# diceee123_2021-04-25_1.net
KiCad netlist of a schematic drawn in EasyEDA
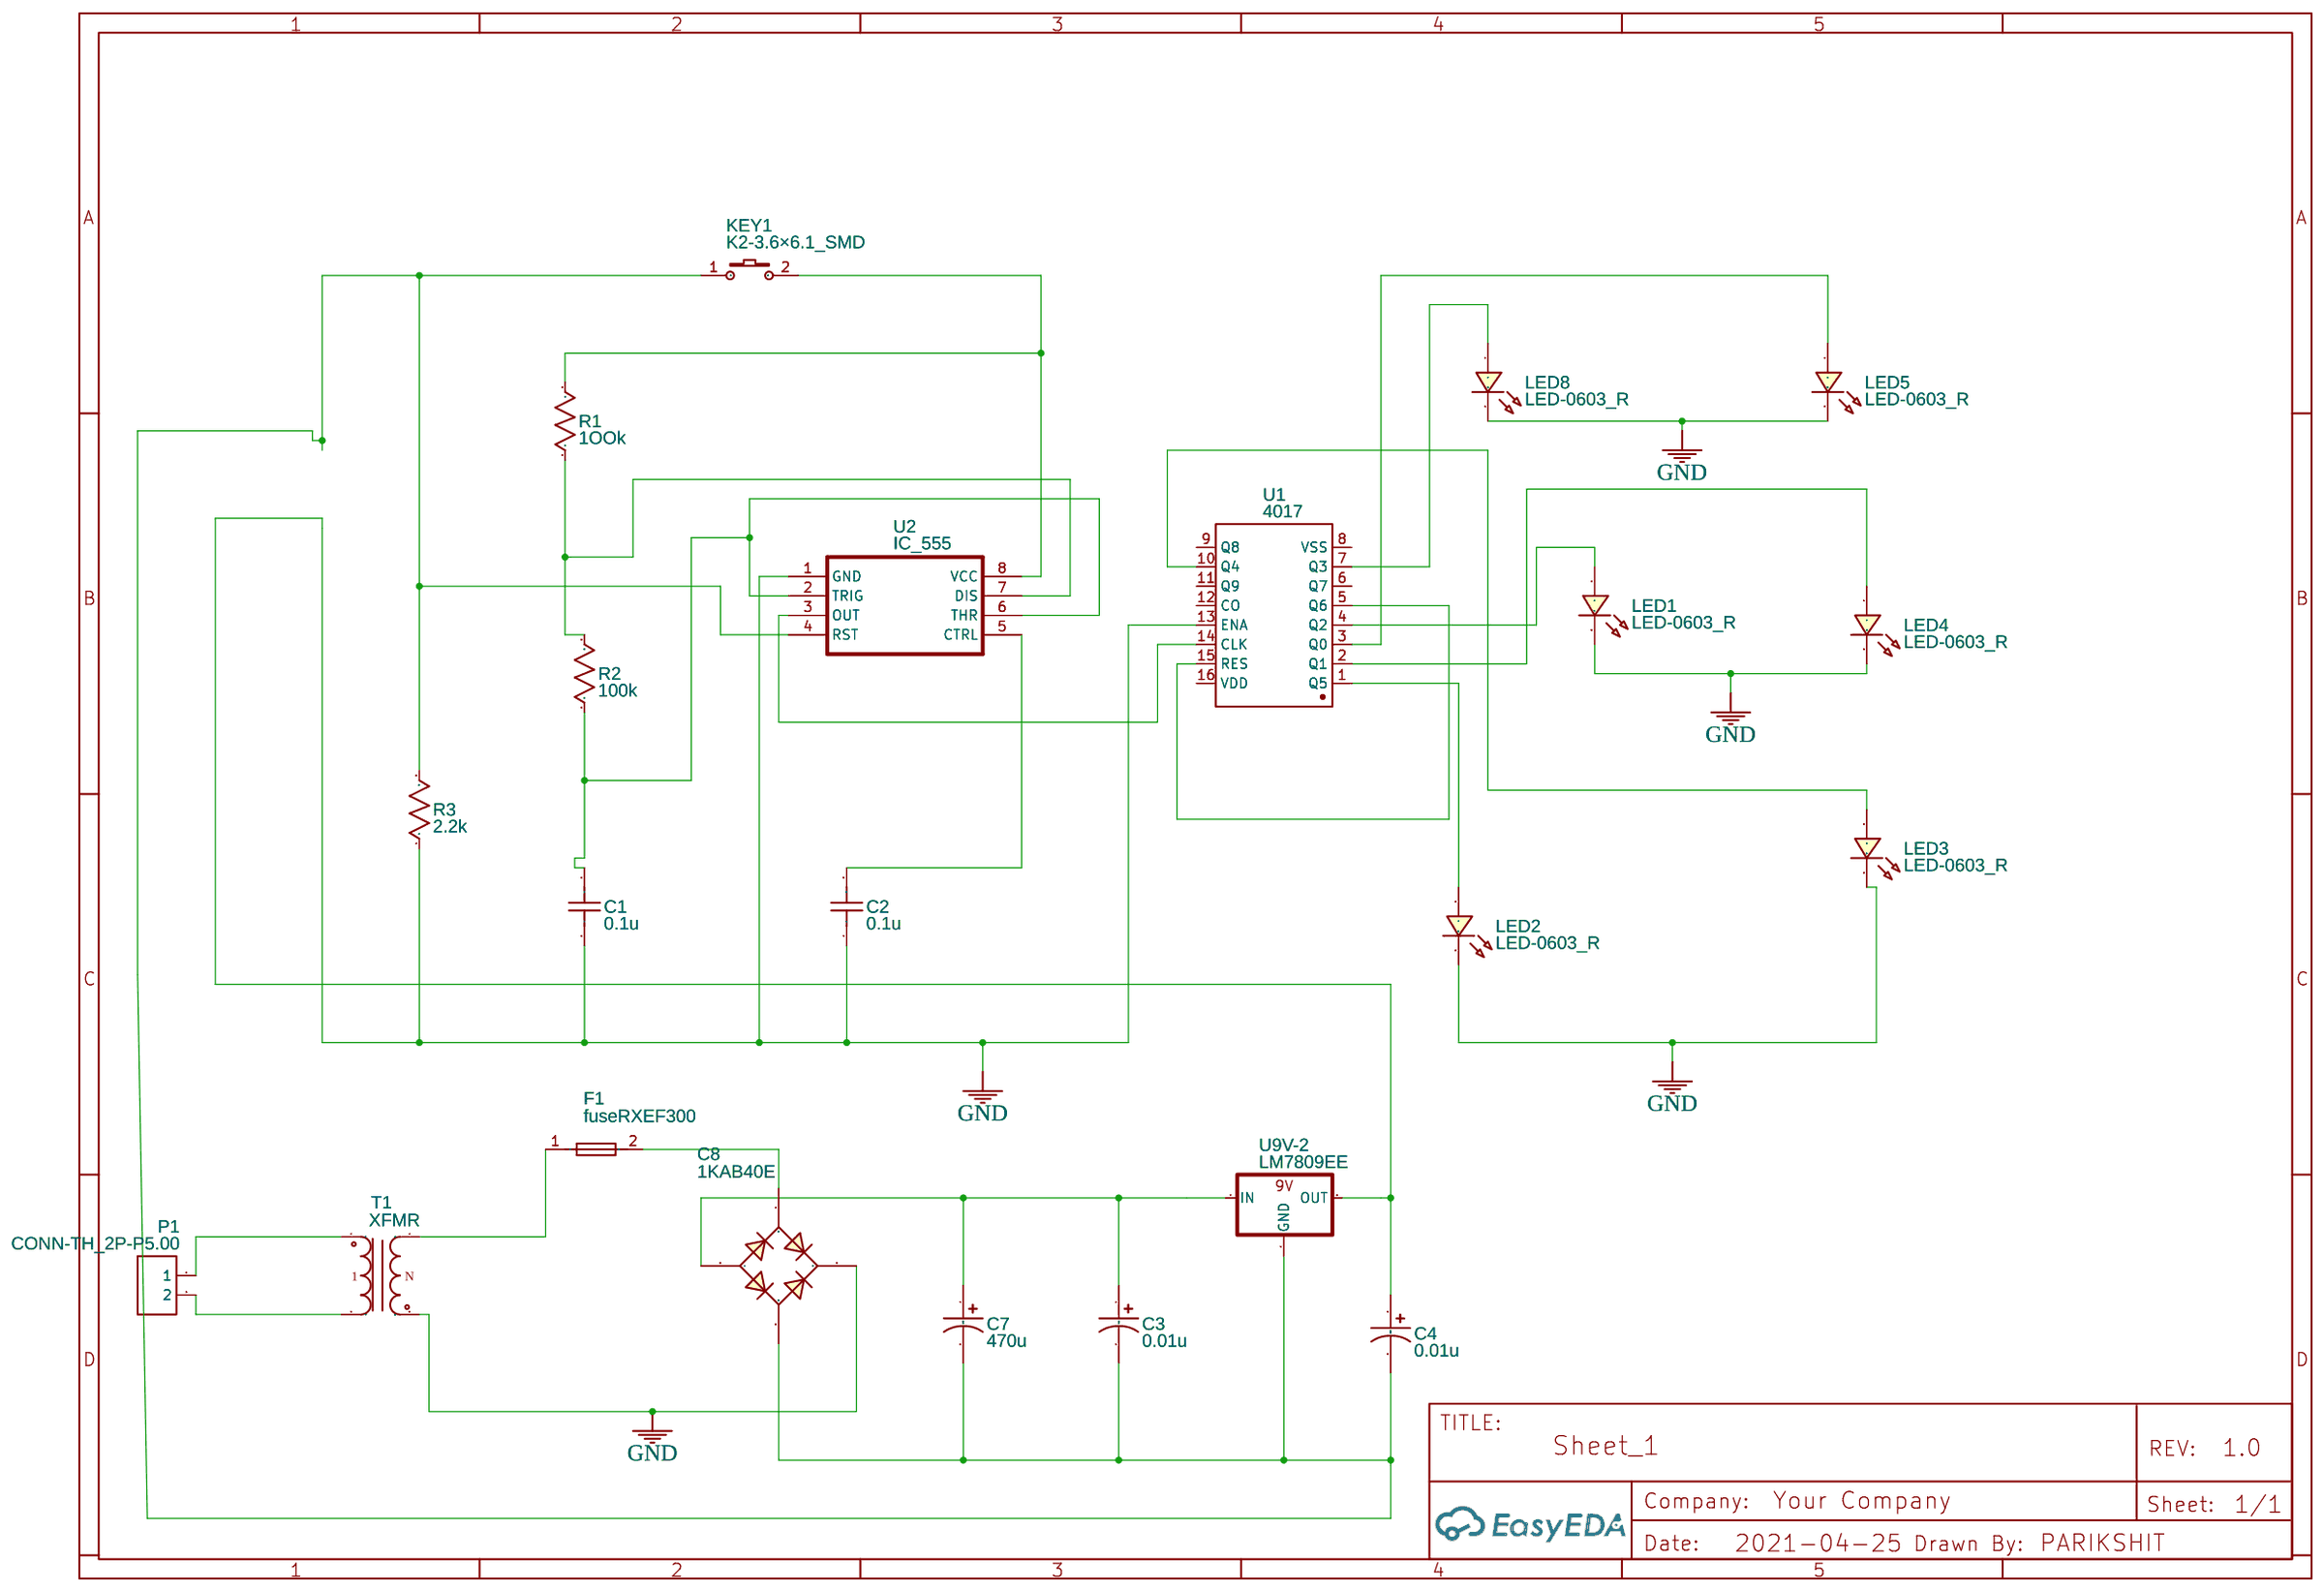
[diagram p0: schematic sheet]

(export (version "E")
  (design (tool "Eeschema 10.0.6"))
  (components
    (comp (ref "C1") (value "0.1u") (libsource (lib "") (part "C_0603_US")))
    (comp (ref "C2") (value "0.1u") (libsource (lib "") (part "C_0603_US")))
    (comp (ref "C3") (value "0.01u") (libsource (lib "") (part "CE_TH_D3.0×F1.5_US")))
    (comp (ref "C4") (value "0.01u") (libsource (lib "") (part "CE_TH_D3.0×F1.5_US")))
    (comp (ref "C7") (value "470u") (libsource (lib "") (part "CE_TH_D3.0×F1.5_US")))
    (comp (ref "C8") (value "1KAB40E") (libsource (lib "") (part "1KAB40E")))
    (comp (ref "F1")
      (value "fuseRXEF300")
      (fields (field (name "BOM_Supplier Part") "C14397"))
      (libsource (lib "") (part "fuseRXEF300"))
    )
    (comp (ref "KEY1")
      (value "K2-3.6×6.1_SMD")
      (fields
        (field (name "BOM_Manufacturer Part") "K2-1107ST-A4SW-06")
        (field (name "BOM_Supplier Part") "C118141")
      )
      (libsource (lib "") (part "K2-3.6×6.1_SMD"))
    )
    (comp (ref "LED1")
      (value "LED-0603_R")
      (fields
        (field (name "BOM_Manufacturer Part") "19-217/R6C-AL1M2VY/3T")
        (field (name "BOM_Supplier Part") "C72044")
      )
      (libsource (lib "") (part "LED-0603_R"))
    )
    (comp (ref "LED2")
      (value "LED-0603_R")
      (fields
        (field (name "BOM_Manufacturer Part") "19-217/R6C-AL1M2VY/3T")
        (field (name "BOM_Supplier Part") "C72044")
      )
      (libsource (lib "") (part "LED-0603_R"))
    )
    (comp (ref "LED3")
      (value "LED-0603_R")
      (fields
        (field (name "BOM_Manufacturer Part") "19-217/R6C-AL1M2VY/3T")
        (field (name "BOM_Supplier Part") "C72044")
      )
      (libsource (lib "") (part "LED-0603_R"))
    )
    (comp (ref "LED4")
      (value "LED-0603_R")
      (fields
        (field (name "BOM_Manufacturer Part") "19-217/R6C-AL1M2VY/3T")
        (field (name "BOM_Supplier Part") "C72044")
      )
      (libsource (lib "") (part "LED-0603_R"))
    )
    (comp (ref "LED5")
      (value "LED-0603_R")
      (fields
        (field (name "BOM_Manufacturer Part") "19-217/R6C-AL1M2VY/3T")
        (field (name "BOM_Supplier Part") "C72044")
      )
      (libsource (lib "") (part "LED-0603_R"))
    )
    (comp (ref "LED8")
      (value "LED-0603_R")
      (fields
        (field (name "BOM_Manufacturer Part") "19-217/R6C-AL1M2VY/3T")
        (field (name "BOM_Supplier Part") "C72044")
      )
      (libsource (lib "") (part "LED-0603_R"))
    )
    (comp (ref "P1") (value "CONN-TH_2P-P5.00") (libsource (lib "") (part "CONN-TH_2P-P5.00")))
    (comp (ref "R1") (value "1OOk") (libsource (lib "") (part "R_0603_US")))
    (comp (ref "R2") (value "100k") (libsource (lib "") (part "R_0603_US")))
    (comp (ref "R3") (value "2.2k") (libsource (lib "") (part "R_0603_US")))
    (comp (ref "T1") (value "XFMR") (libsource (lib "") (part "XFMR")))
    (comp (ref "U1") (value "4017") (libsource (lib "") (part "4017")))
    (comp (ref "U2") (value "IC_555") (libsource (lib "") (part "IC_555")))
    (comp (ref "U9V-2") (value "LM7809EE") (libsource (lib "") (part "7809")))
  )
  (nets
    (net (code "1") (name "GND") (class "Default")
      (node (ref "C1") (pin "1") (pinfunction "1_1") (pintype "unspecified"))
      (node (ref "C2") (pin "1") (pinfunction "1_1") (pintype "unspecified"))
      (node (ref "C4") (pin "1") (pinfunction "1_1") (pintype "unspecified"))
      (node (ref "C8") (pin "1") (pinfunction "K_1") (pintype "unspecified"))
      (node (ref "LED1") (pin "2") (pinfunction "2_2") (pintype "unspecified"))
      (node (ref "LED2") (pin "2") (pinfunction "2_2") (pintype "unspecified"))
      (node (ref "LED3") (pin "2") (pinfunction "2_2") (pintype "unspecified"))
      (node (ref "LED4") (pin "2") (pinfunction "2_2") (pintype "unspecified"))
      (node (ref "LED5") (pin "2") (pinfunction "2_2") (pintype "unspecified"))
      (node (ref "LED8") (pin "2") (pinfunction "2_2") (pintype "unspecified"))
      (node (ref "R3") (pin "1") (pinfunction "1_1") (pintype "unspecified"))
      (node (ref "T1") (pin "3") (pinfunction "3_3") (pintype "unspecified"))
      (node (ref "U1") (pin "13") (pinfunction "ENA_13") (pintype "unspecified"))
      (node (ref "U2") (pin "1") (pinfunction "GND_1") (pintype "unspecified"))
      (node (ref "U9V-2") (pin "3") (pinfunction "OUT_3") (pintype "unspecified"))
    )
    (net (code "2") (name "Net-(C8-A)") (class "Default")
      (node (ref "C3") (pin "1") (pinfunction "1_1") (pintype "unspecified"))
      (node (ref "C7") (pin "1") (pinfunction "1_1") (pintype "unspecified"))
      (node (ref "C8") (pin "3") (pinfunction "A_3") (pintype "unspecified"))
      (node (ref "U9V-2") (pin "1") (pinfunction "IN_1") (pintype "unspecified"))
    )
    (net (code "3") (name "Net-(C8-C-Pad4)") (class "Default")
      (node (ref "C8") (pin "4") (pinfunction "C_4") (pintype "unspecified"))
      (node (ref "F1") (pin "2") (pinfunction "2_2") (pintype "unspecified"))
    )
    (net (code "4") (name "Net-(F1-Pad1)") (class "Default")
      (node (ref "F1") (pin "1") (pinfunction "1_1") (pintype "unspecified"))
      (node (ref "T1") (pin "4") (pinfunction "4_4") (pintype "unspecified"))
    )
    (net (code "5") (name "Net-(P1-Pad1)") (class "Default")
      (node (ref "P1") (pin "1") (pinfunction "1_1") (pintype "unspecified"))
      (node (ref "T1") (pin "1") (pinfunction "1_1") (pintype "unspecified"))
    )
    (net (code "6") (name "Net-(P1-Pad2)") (class "Default")
      (node (ref "P1") (pin "2") (pinfunction "2_2") (pintype "unspecified"))
      (node (ref "T1") (pin "2") (pinfunction "2_2") (pintype "unspecified"))
    )
    (net (code "7") (name "Net-(U1-CLK)") (class "Default")
      (node (ref "U1") (pin "14") (pinfunction "CLK_14") (pintype "unspecified"))
      (node (ref "U2") (pin "3") (pinfunction "OUT_3") (pintype "output"))
    )
    (net (code "8") (name "Net-(U1-Q0)") (class "Default")
      (node (ref "LED5") (pin "1") (pinfunction "1_1") (pintype "unspecified"))
      (node (ref "U1") (pin "3") (pinfunction "Q0_3") (pintype "unspecified"))
    )
    (net (code "9") (name "Net-(U1-Q1)") (class "Default")
      (node (ref "LED4") (pin "1") (pinfunction "1_1") (pintype "unspecified"))
      (node (ref "U1") (pin "2") (pinfunction "Q1_2") (pintype "unspecified"))
    )
    (net (code "10") (name "Net-(U1-Q2)") (class "Default")
      (node (ref "LED1") (pin "1") (pinfunction "1_1") (pintype "unspecified"))
      (node (ref "U1") (pin "4") (pinfunction "Q2_4") (pintype "unspecified"))
    )
    (net (code "11") (name "Net-(U1-Q3)") (class "Default")
      (node (ref "LED8") (pin "1") (pinfunction "1_1") (pintype "unspecified"))
      (node (ref "U1") (pin "7") (pinfunction "Q3_7") (pintype "unspecified"))
    )
    (net (code "12") (name "Net-(U1-Q4)") (class "Default")
      (node (ref "LED3") (pin "1") (pinfunction "1_1") (pintype "unspecified"))
      (node (ref "U1") (pin "10") (pinfunction "Q4_10") (pintype "unspecified"))
    )
    (net (code "13") (name "Net-(U1-Q5)") (class "Default")
      (node (ref "LED2") (pin "1") (pinfunction "1_1") (pintype "unspecified"))
      (node (ref "U1") (pin "1") (pinfunction "Q5_1") (pintype "unspecified"))
    )
    (net (code "14") (name "Net-(U1-Q6)") (class "Default")
      (node (ref "U1") (pin "15") (pinfunction "RES_15") (pintype "unspecified"))
      (node (ref "U1") (pin "5") (pinfunction "Q6_5") (pintype "unspecified"))
    )
    (net (code "15") (name "Net-(U2-CTRL)") (class "Default")
      (node (ref "C2") (pin "2") (pinfunction "2_2") (pintype "unspecified"))
      (node (ref "U2") (pin "5") (pinfunction "CTRL_5") (pintype "unspecified"))
    )
    (net (code "16") (name "Net-(U2-DIS)") (class "Default")
      (node (ref "R1") (pin "1") (pinfunction "1_1") (pintype "unspecified"))
      (node (ref "R2") (pin "2") (pinfunction "2_2") (pintype "unspecified"))
      (node (ref "U2") (pin "7") (pinfunction "DIS_7") (pintype "input"))
    )
    (net (code "17") (name "Net-(U2-RST)") (class "Default")
      (node (ref "C3") (pin "2") (pinfunction "2_2") (pintype "unspecified"))
      (node (ref "C4") (pin "2") (pinfunction "2_2") (pintype "unspecified"))
      (node (ref "C7") (pin "2") (pinfunction "2_2") (pintype "unspecified"))
      (node (ref "C8") (pin "2") (pinfunction "C_2") (pintype "unspecified"))
      (node (ref "KEY1") (pin "1") (pinfunction "1_1") (pintype "unspecified"))
      (node (ref "R3") (pin "2") (pinfunction "2_2") (pintype "unspecified"))
      (node (ref "U2") (pin "4") (pinfunction "RST_4") (pintype "input"))
      (node (ref "U9V-2") (pin "2") (pinfunction "GND_2") (pintype "unspecified"))
    )
    (net (code "18") (name "Net-(U2-THR)") (class "Default")
      (node (ref "C1") (pin "2") (pinfunction "2_2") (pintype "unspecified"))
      (node (ref "R2") (pin "1") (pinfunction "1_1") (pintype "unspecified"))
      (node (ref "U2") (pin "2") (pinfunction "TRIG_2") (pintype "input"))
      (node (ref "U2") (pin "6") (pinfunction "THR_6") (pintype "input"))
    )
    (net (code "19") (name "Net-(U2-VCC)") (class "Default")
      (node (ref "KEY1") (pin "2") (pinfunction "2_2") (pintype "unspecified"))
      (node (ref "R1") (pin "2") (pinfunction "2_2") (pintype "unspecified"))
      (node (ref "U2") (pin "8") (pinfunction "VCC_8") (pintype "unspecified"))
    )
    (net (code "20") (name "unconnected-(U1-CO-Pad12)") (class "Default")
      (node (ref "U1") (pin "12") (pinfunction "CO_12") (pintype "unspecified"))
    )
    (net (code "21") (name "unconnected-(U1-Q7-Pad6)") (class "Default")
      (node (ref "U1") (pin "6") (pinfunction "Q7_6") (pintype "unspecified"))
    )
    (net (code "22") (name "unconnected-(U1-Q8-Pad9)") (class "Default")
      (node (ref "U1") (pin "9") (pinfunction "Q8_9") (pintype "unspecified"))
    )
    (net (code "23") (name "unconnected-(U1-Q9-Pad11)") (class "Default")
      (node (ref "U1") (pin "11") (pinfunction "Q9_11") (pintype "unspecified"))
    )
    (net (code "24") (name "unconnected-(U1-VDD-Pad16)") (class "Default")
      (node (ref "U1") (pin "16") (pinfunction "VDD_16") (pintype "unspecified"))
    )
    (net (code "25") (name "unconnected-(U1-VSS-Pad8)") (class "Default")
      (node (ref "U1") (pin "8") (pinfunction "VSS_8") (pintype "unspecified"))
    )
  )
)
